# processor_breakout_conn.net
KiCad netlist of a schematic drawn in Altium Designer
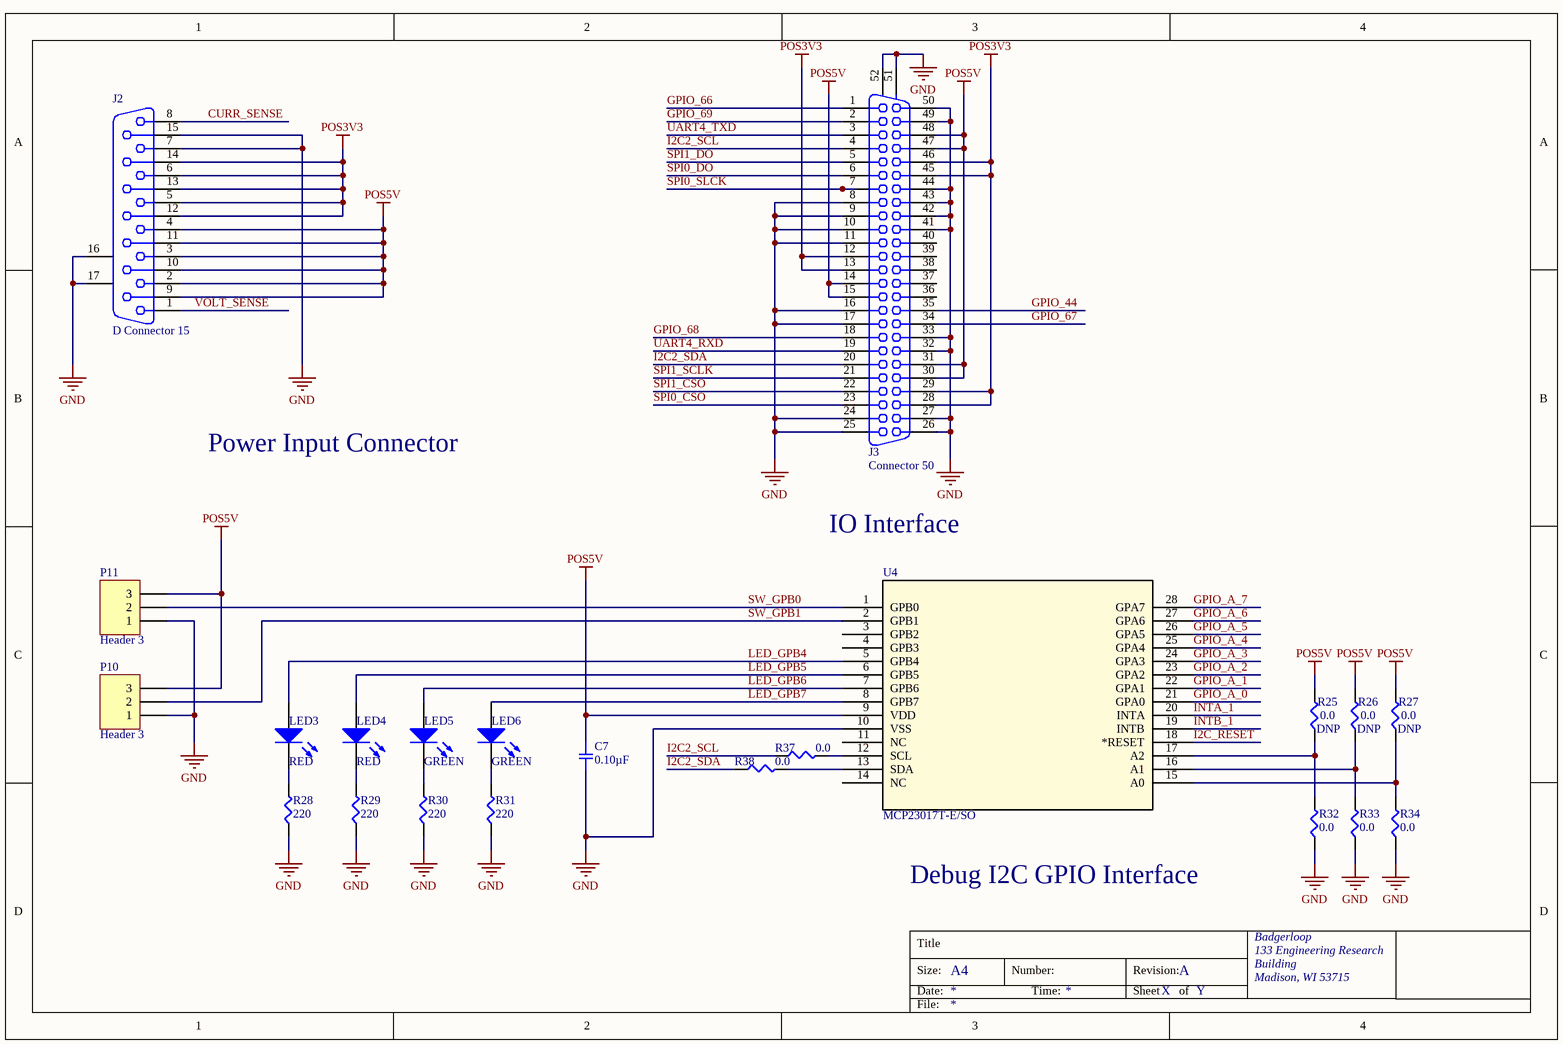
[diagram p0: processor_breakout_conn.SchDoc]

(export (version "E")
  (design (tool "Eeschema 10.0.6"))
  (components
    (comp (ref "C7")
      (value "0.10µF")
      (footprint "SMD-0603C")
      (description "CAP CER 0.1UF 100V X7R 0603")
      (fields
        (field (name "DIGI-KEY PART NUMBER") "490-13420-1-ND")
        (field (name "PART NUMBER") "GCJ188R72A104KA01D")
      )
      (libsource (lib "capacitor") (part "GCJ188R72A104KA01D"))
    )
    (comp (ref "J2")
      (value "D Connector 15")
      (footprint "DSUB1.385-2H15")
      (description "Receptacle Assembly, 15 Position, Right Angle")
      (fields (field (name "PUBLISHER") "Altium Limited"))
      (libsource (lib "connector") (part "D Connector 15"))
    )
    (comp (ref "J3")
      (value "Connector 50")
      (footprint "050DSUB1.27-H96")
      (description "Receptacle Header Assemby")
      (fields (field (name "PUBLISHER") "Altium Limited"))
      (libsource (lib "temp") (part "Connector 50"))
    )
    (comp (ref "LED3")
      (value "RED")
      (footprint "LED 0603 RED")
      (description "Red 631nm LED Indication - Discrete 2V 0603 (1608 Metric)")
      (fields (field (name "MANUFACTURER") "Lite-On Inc."))
      (libsource (lib "misc") (part "LED RED 0603"))
    )
    (comp (ref "LED4")
      (value "RED")
      (footprint "LED 0603 RED")
      (description "Red 631nm LED Indication - Discrete 2V 0603 (1608 Metric)")
      (fields (field (name "MANUFACTURER") "Lite-On Inc."))
      (libsource (lib "misc") (part "LED RED 0603"))
    )
    (comp (ref "LED5")
      (value "GREEN")
      (footprint "LED 0603 GREEN")
      (fields (field (name "MANUFACTURER") "Lite-On Inc."))
      (libsource (lib "misc") (part "LED GREEN 0603"))
    )
    (comp (ref "LED6")
      (value "GREEN")
      (footprint "LED 0603 GREEN")
      (fields (field (name "MANUFACTURER") "Lite-On Inc."))
      (libsource (lib "misc") (part "LED GREEN 0603"))
    )
    (comp (ref "P10")
      (value "Header 3")
      (footprint "Pin Header 1x3 TH Pitch 2.54mm")
      (description "Header, 3-Pin")
      (fields (field (name "PUBLISHER") "Altium Limited"))
      (libsource (lib "connector") (part "Header 3"))
    )
    (comp (ref "P11")
      (value "Header 3")
      (footprint "Pin Header 1x3 TH Pitch 2.54mm")
      (description "Header, 3-Pin")
      (fields (field (name "PUBLISHER") "Altium Limited"))
      (libsource (lib "connector") (part "Header 3"))
    )
    (comp (ref "R25")
      (value "0.0")
      (footprint "SMD-0402-RES")
      (description "RES SMD 0.0OHM JUMPER 1/10W 0402")
      (fields
        (field (name "PART NUMBER") "ERJ-2GE0R00X")
        (field (name "DIGI-KEY PART NUMBER") "P0.0JCT-ND")
        (field (name "DNP") "DNP")
      )
      (libsource (lib "resistor") (part "ERJ-2GE0R00X"))
    )
    (comp (ref "R26")
      (value "0.0")
      (footprint "SMD-0402-RES")
      (description "RES SMD 0.0OHM JUMPER 1/10W 0402")
      (fields
        (field (name "PART NUMBER") "ERJ-2GE0R00X")
        (field (name "DIGI-KEY PART NUMBER") "P0.0JCT-ND")
        (field (name "DNP") "DNP")
      )
      (libsource (lib "resistor") (part "ERJ-2GE0R00X"))
    )
    (comp (ref "R27")
      (value "0.0")
      (footprint "SMD-0402-RES")
      (description "RES SMD 0.0OHM JUMPER 1/10W 0402")
      (fields
        (field (name "PART NUMBER") "ERJ-2GE0R00X")
        (field (name "DIGI-KEY PART NUMBER") "P0.0JCT-ND")
        (field (name "DNP") "DNP")
      )
      (libsource (lib "resistor") (part "ERJ-2GE0R00X"))
    )
    (comp (ref "R28")
      (value "220")
      (footprint "SMD-0805-RES")
      (description "RES SMD 220 OHM 1% 1/8W 0805")
      (fields (field (name "PART NUMBER") "ERJ-6ENF2200V") (field (name "DIGI-KEY PART NUMBER") "P220CCT-ND"))
      (libsource (lib "resistor") (part "ERJ-6ENF2200V"))
    )
    (comp (ref "R29")
      (value "220")
      (footprint "SMD-0805-RES")
      (description "RES SMD 220 OHM 1% 1/8W 0805")
      (fields (field (name "PART NUMBER") "ERJ-6ENF2200V") (field (name "DIGI-KEY PART NUMBER") "P220CCT-ND"))
      (libsource (lib "resistor") (part "ERJ-6ENF2200V"))
    )
    (comp (ref "R30")
      (value "220")
      (footprint "SMD-0805-RES")
      (description "RES SMD 220 OHM 1% 1/8W 0805")
      (fields (field (name "PART NUMBER") "ERJ-6ENF2200V") (field (name "DIGI-KEY PART NUMBER") "P220CCT-ND"))
      (libsource (lib "resistor") (part "ERJ-6ENF2200V"))
    )
    (comp (ref "R31")
      (value "220")
      (footprint "SMD-0805-RES")
      (description "RES SMD 220 OHM 1% 1/8W 0805")
      (fields (field (name "PART NUMBER") "ERJ-6ENF2200V") (field (name "DIGI-KEY PART NUMBER") "P220CCT-ND"))
      (libsource (lib "resistor") (part "ERJ-6ENF2200V"))
    )
    (comp (ref "R32")
      (value "0.0")
      (footprint "SMD-0402-RES")
      (description "RES SMD 0.0OHM JUMPER 1/10W 0402")
      (fields (field (name "PART NUMBER") "ERJ-2GE0R00X") (field (name "DIGI-KEY PART NUMBER") "P0.0JCT-ND"))
      (libsource (lib "resistor") (part "ERJ-2GE0R00X"))
    )
    (comp (ref "R33")
      (value "0.0")
      (footprint "SMD-0402-RES")
      (description "RES SMD 0.0OHM JUMPER 1/10W 0402")
      (fields (field (name "PART NUMBER") "ERJ-2GE0R00X") (field (name "DIGI-KEY PART NUMBER") "P0.0JCT-ND"))
      (libsource (lib "resistor") (part "ERJ-2GE0R00X"))
    )
    (comp (ref "R34")
      (value "0.0")
      (footprint "SMD-0402-RES")
      (description "RES SMD 0.0OHM JUMPER 1/10W 0402")
      (fields (field (name "PART NUMBER") "ERJ-2GE0R00X") (field (name "DIGI-KEY PART NUMBER") "P0.0JCT-ND"))
      (libsource (lib "resistor") (part "ERJ-2GE0R00X"))
    )
    (comp (ref "R37")
      (value "0.0")
      (footprint "SMD-0402-RES")
      (description "RES SMD 0.0OHM JUMPER 1/10W 0402")
      (fields (field (name "PART NUMBER") "ERJ-2GE0R00X") (field (name "DIGI-KEY PART NUMBER") "P0.0JCT-ND"))
      (libsource (lib "resistor") (part "ERJ-2GE0R00X"))
    )
    (comp (ref "R38")
      (value "0.0")
      (footprint "SMD-0402-RES")
      (description "RES SMD 0.0OHM JUMPER 1/10W 0402")
      (fields (field (name "PART NUMBER") "ERJ-2GE0R00X") (field (name "DIGI-KEY PART NUMBER") "P0.0JCT-ND"))
      (libsource (lib "resistor") (part "ERJ-2GE0R00X"))
    )
    (comp (ref "U4")
      (value "MCP23017T-E/SO")
      (footprint "SOIC28-W_MC-M")
      (description "Imported")
      (libsource (lib "temp") (part "MCP23017T-E/SO"))
    )
  )
  (nets
    (net (code "1") (name "/CURR_SENSE") (class "Default")
      (node (ref "J2") (pin "8") (pinfunction "8_8") (pintype "passive"))
    )
    (net (code "2") (name "/GPIO_44") (class "Default")
      (node (ref "J3") (pin "35") (pinfunction "35_35") (pintype "passive"))
    )
    (net (code "3") (name "/GPIO_66") (class "Default")
      (node (ref "J3") (pin "1") (pinfunction "1_1") (pintype "passive"))
    )
    (net (code "4") (name "/GPIO_67") (class "Default")
      (node (ref "J3") (pin "34") (pinfunction "34_34") (pintype "passive"))
    )
    (net (code "5") (name "/GPIO_68") (class "Default")
      (node (ref "J3") (pin "18") (pinfunction "18_18") (pintype "passive"))
    )
    (net (code "6") (name "/GPIO_69") (class "Default")
      (node (ref "J3") (pin "2") (pinfunction "2_2") (pintype "passive"))
    )
    (net (code "7") (name "/GPIO_A_0") (class "Default")
      (node (ref "U4") (pin "21") (pinfunction "GPA0_21") (pintype "passive"))
    )
    (net (code "8") (name "/GPIO_A_1") (class "Default")
      (node (ref "U4") (pin "22") (pinfunction "GPA1_22") (pintype "passive"))
    )
    (net (code "9") (name "/GPIO_A_2") (class "Default")
      (node (ref "U4") (pin "23") (pinfunction "GPA2_23") (pintype "passive"))
    )
    (net (code "10") (name "/GPIO_A_3") (class "Default")
      (node (ref "U4") (pin "24") (pinfunction "GPA3_24") (pintype "passive"))
    )
    (net (code "11") (name "/GPIO_A_4") (class "Default")
      (node (ref "U4") (pin "25") (pinfunction "GPA4_25") (pintype "passive"))
    )
    (net (code "12") (name "/GPIO_A_5") (class "Default")
      (node (ref "U4") (pin "26") (pinfunction "GPA5_26") (pintype "passive"))
    )
    (net (code "13") (name "/GPIO_A_6") (class "Default")
      (node (ref "U4") (pin "27") (pinfunction "GPA6_27") (pintype "passive"))
    )
    (net (code "14") (name "/GPIO_A_7") (class "Default")
      (node (ref "U4") (pin "28") (pinfunction "GPA7_28") (pintype "passive"))
    )
    (net (code "15") (name "/I2C2_SCL") (class "Default")
      (node (ref "J3") (pin "4") (pinfunction "4_4") (pintype "passive"))
      (node (ref "R37") (pin "1") (pinfunction "1_1") (pintype "passive"))
    )
    (net (code "16") (name "/I2C2_SDA") (class "Default")
      (node (ref "J3") (pin "20") (pinfunction "20_20") (pintype "passive"))
      (node (ref "R38") (pin "1") (pinfunction "1_1") (pintype "passive"))
    )
    (net (code "17") (name "/I2C_RESET") (class "Default")
      (node (ref "U4") (pin "18") (pinfunction "*RESET_18") (pintype "passive"))
    )
    (net (code "18") (name "/INTA_1") (class "Default")
      (node (ref "U4") (pin "20") (pinfunction "INTA_20") (pintype "passive"))
    )
    (net (code "19") (name "/INTB_1") (class "Default")
      (node (ref "U4") (pin "19") (pinfunction "INTB_19") (pintype "passive"))
    )
    (net (code "20") (name "/LED_GPB4") (class "Default")
      (node (ref "LED3") (pin "1") (pinfunction "A_1") (pintype "passive"))
      (node (ref "U4") (pin "5") (pinfunction "GPB4_5") (pintype "passive"))
    )
    (net (code "21") (name "/LED_GPB5") (class "Default")
      (node (ref "LED4") (pin "1") (pinfunction "A_1") (pintype "passive"))
      (node (ref "U4") (pin "6") (pinfunction "GPB5_6") (pintype "passive"))
    )
    (net (code "22") (name "/LED_GPB6") (class "Default")
      (node (ref "LED5") (pin "1") (pinfunction "A_1") (pintype "passive"))
      (node (ref "U4") (pin "7") (pinfunction "GPB6_7") (pintype "passive"))
    )
    (net (code "23") (name "/LED_GPB7") (class "Default")
      (node (ref "LED6") (pin "1") (pinfunction "A_1") (pintype "passive"))
      (node (ref "U4") (pin "8") (pinfunction "GPB7_8") (pintype "passive"))
    )
    (net (code "24") (name "/SPI0_CSO") (class "Default")
      (node (ref "J3") (pin "23") (pinfunction "23_23") (pintype "passive"))
    )
    (net (code "25") (name "/SPI0_DO") (class "Default")
      (node (ref "J3") (pin "6") (pinfunction "6_6") (pintype "passive"))
    )
    (net (code "26") (name "/SPI0_SLCK") (class "Default")
      (node (ref "J3") (pin "7") (pinfunction "7_7") (pintype "passive"))
    )
    (net (code "27") (name "/SPI1_CSO") (class "Default")
      (node (ref "J3") (pin "22") (pinfunction "22_22") (pintype "passive"))
    )
    (net (code "28") (name "/SPI1_DO") (class "Default")
      (node (ref "J3") (pin "5") (pinfunction "5_5") (pintype "passive"))
    )
    (net (code "29") (name "/SPI1_SCLK") (class "Default")
      (node (ref "J3") (pin "21") (pinfunction "21_21") (pintype "passive"))
    )
    (net (code "30") (name "/SW_GPB0") (class "Default")
      (node (ref "P11") (pin "2") (pinfunction "2_2") (pintype "passive"))
      (node (ref "U4") (pin "1") (pinfunction "GPB0_1") (pintype "passive"))
    )
    (net (code "31") (name "/SW_GPB1") (class "Default")
      (node (ref "P10") (pin "2") (pinfunction "2_2") (pintype "passive"))
      (node (ref "U4") (pin "2") (pinfunction "GPB1_2") (pintype "passive"))
    )
    (net (code "32") (name "/UART4_RXD") (class "Default")
      (node (ref "J3") (pin "19") (pinfunction "19_19") (pintype "passive"))
    )
    (net (code "33") (name "/UART4_TXD") (class "Default")
      (node (ref "J3") (pin "3") (pinfunction "3_3") (pintype "passive"))
    )
    (net (code "34") (name "/VOLT_SENSE") (class "Default")
      (node (ref "J2") (pin "1") (pinfunction "1_1") (pintype "passive"))
    )
    (net (code "35") (name "GND") (class "Default")
      (node (ref "C7") (pin "2") (pinfunction "2_2") (pintype "passive"))
      (node (ref "J2") (pin "15") (pinfunction "15_15") (pintype "passive"))
      (node (ref "J2") (pin "16") (pinfunction "MH1_16") (pintype "passive"))
      (node (ref "J2") (pin "17") (pinfunction "MH2_17") (pintype "passive"))
      (node (ref "J2") (pin "7") (pinfunction "7_7") (pintype "passive"))
      (node (ref "J3") (pin "10") (pinfunction "10_10") (pintype "passive"))
      (node (ref "J3") (pin "11") (pinfunction "11_11") (pintype "passive"))
      (node (ref "J3") (pin "16") (pinfunction "16_16") (pintype "passive"))
      (node (ref "J3") (pin "17") (pinfunction "17_17") (pintype "passive"))
      (node (ref "J3") (pin "24") (pinfunction "24_24") (pintype "passive"))
      (node (ref "J3") (pin "25") (pinfunction "25_25") (pintype "passive"))
      (node (ref "J3") (pin "26") (pinfunction "26_26") (pintype "passive"))
      (node (ref "J3") (pin "27") (pinfunction "27_27") (pintype "passive"))
      (node (ref "J3") (pin "32") (pinfunction "32_32") (pintype "passive"))
      (node (ref "J3") (pin "33") (pinfunction "33_33") (pintype "passive"))
      (node (ref "J3") (pin "41") (pinfunction "41_41") (pintype "passive"))
      (node (ref "J3") (pin "42") (pinfunction "42_42") (pintype "passive"))
      (node (ref "J3") (pin "43") (pinfunction "43_43") (pintype "passive"))
      (node (ref "J3") (pin "44") (pinfunction "44_44") (pintype "passive"))
      (node (ref "J3") (pin "49") (pinfunction "49_49") (pintype "passive"))
      (node (ref "J3") (pin "50") (pinfunction "50_50") (pintype "passive"))
      (node (ref "J3") (pin "51") (pinfunction "51_51") (pintype "passive"))
      (node (ref "J3") (pin "52") (pinfunction "52_52") (pintype "passive"))
      (node (ref "J3") (pin "8") (pinfunction "8_8") (pintype "passive"))
      (node (ref "J3") (pin "9") (pinfunction "9_9") (pintype "passive"))
      (node (ref "P10") (pin "1") (pinfunction "1_1") (pintype "passive"))
      (node (ref "P11") (pin "1") (pinfunction "1_1") (pintype "passive"))
      (node (ref "R28") (pin "1") (pinfunction "1_1") (pintype "passive"))
      (node (ref "R29") (pin "1") (pinfunction "1_1") (pintype "passive"))
      (node (ref "R30") (pin "1") (pinfunction "1_1") (pintype "passive"))
      (node (ref "R31") (pin "1") (pinfunction "1_1") (pintype "passive"))
      (node (ref "R32") (pin "1") (pinfunction "1_1") (pintype "passive"))
      (node (ref "R33") (pin "1") (pinfunction "1_1") (pintype "passive"))
      (node (ref "R34") (pin "1") (pinfunction "1_1") (pintype "passive"))
      (node (ref "U4") (pin "10") (pinfunction "VSS_10") (pintype "passive"))
    )
    (net (code "36") (name "Net-(LED3-K)") (class "Default")
      (node (ref "LED3") (pin "2") (pinfunction "K_2") (pintype "passive"))
      (node (ref "R28") (pin "2") (pinfunction "2_2") (pintype "passive"))
    )
    (net (code "37") (name "Net-(LED4-K)") (class "Default")
      (node (ref "LED4") (pin "2") (pinfunction "K_2") (pintype "passive"))
      (node (ref "R29") (pin "2") (pinfunction "2_2") (pintype "passive"))
    )
    (net (code "38") (name "Net-(LED5-K)") (class "Default")
      (node (ref "LED5") (pin "2") (pinfunction "K_2") (pintype "passive"))
      (node (ref "R30") (pin "2") (pinfunction "2_2") (pintype "passive"))
    )
    (net (code "39") (name "Net-(LED6-K)") (class "Default")
      (node (ref "LED6") (pin "2") (pinfunction "K_2") (pintype "passive"))
      (node (ref "R31") (pin "2") (pinfunction "2_2") (pintype "passive"))
    )
    (net (code "40") (name "Net-(U4-A0)") (class "Default")
      (node (ref "R27") (pin "1") (pinfunction "1_1") (pintype "passive"))
      (node (ref "R34") (pin "2") (pinfunction "2_2") (pintype "passive"))
      (node (ref "U4") (pin "15") (pinfunction "A0_15") (pintype "passive"))
    )
    (net (code "41") (name "Net-(U4-A1)") (class "Default")
      (node (ref "R26") (pin "1") (pinfunction "1_1") (pintype "passive"))
      (node (ref "R33") (pin "2") (pinfunction "2_2") (pintype "passive"))
      (node (ref "U4") (pin "16") (pinfunction "A1_16") (pintype "passive"))
    )
    (net (code "42") (name "Net-(U4-A2)") (class "Default")
      (node (ref "R25") (pin "1") (pinfunction "1_1") (pintype "passive"))
      (node (ref "R32") (pin "2") (pinfunction "2_2") (pintype "passive"))
      (node (ref "U4") (pin "17") (pinfunction "A2_17") (pintype "passive"))
    )
    (net (code "43") (name "Net-(U4-SCL)") (class "Default")
      (node (ref "R37") (pin "2") (pinfunction "2_2") (pintype "passive"))
      (node (ref "U4") (pin "12") (pinfunction "SCL_12") (pintype "passive"))
    )
    (net (code "44") (name "Net-(U4-SDA)") (class "Default")
      (node (ref "R38") (pin "2") (pinfunction "2_2") (pintype "passive"))
      (node (ref "U4") (pin "13") (pinfunction "SDA_13") (pintype "passive"))
    )
    (net (code "45") (name "POS3V3") (class "Default")
      (node (ref "J2") (pin "12") (pinfunction "12_12") (pintype "passive"))
      (node (ref "J2") (pin "13") (pinfunction "13_13") (pintype "passive"))
      (node (ref "J2") (pin "14") (pinfunction "14_14") (pintype "passive"))
      (node (ref "J2") (pin "5") (pinfunction "5_5") (pintype "passive"))
      (node (ref "J2") (pin "6") (pinfunction "6_6") (pintype "passive"))
      (node (ref "J3") (pin "12") (pinfunction "12_12") (pintype "passive"))
      (node (ref "J3") (pin "13") (pinfunction "13_13") (pintype "passive"))
      (node (ref "J3") (pin "28") (pinfunction "28_28") (pintype "passive"))
      (node (ref "J3") (pin "29") (pinfunction "29_29") (pintype "passive"))
      (node (ref "J3") (pin "45") (pinfunction "45_45") (pintype "passive"))
      (node (ref "J3") (pin "46") (pinfunction "46_46") (pintype "passive"))
    )
    (net (code "46") (name "POS5V") (class "Default")
      (node (ref "C7") (pin "1") (pinfunction "1_1") (pintype "passive"))
      (node (ref "J2") (pin "10") (pinfunction "10_10") (pintype "passive"))
      (node (ref "J2") (pin "11") (pinfunction "11_11") (pintype "passive"))
      (node (ref "J2") (pin "2") (pinfunction "2_2") (pintype "passive"))
      (node (ref "J2") (pin "3") (pinfunction "3_3") (pintype "passive"))
      (node (ref "J2") (pin "4") (pinfunction "4_4") (pintype "passive"))
      (node (ref "J2") (pin "9") (pinfunction "9_9") (pintype "passive"))
      (node (ref "J3") (pin "14") (pinfunction "14_14") (pintype "passive"))
      (node (ref "J3") (pin "15") (pinfunction "15_15") (pintype "passive"))
      (node (ref "J3") (pin "30") (pinfunction "30_30") (pintype "passive"))
      (node (ref "J3") (pin "31") (pinfunction "31_31") (pintype "passive"))
      (node (ref "J3") (pin "47") (pinfunction "47_47") (pintype "passive"))
      (node (ref "J3") (pin "48") (pinfunction "48_48") (pintype "passive"))
      (node (ref "P10") (pin "3") (pinfunction "3_3") (pintype "passive"))
      (node (ref "P11") (pin "3") (pinfunction "3_3") (pintype "passive"))
      (node (ref "R25") (pin "2") (pinfunction "2_2") (pintype "passive"))
      (node (ref "R26") (pin "2") (pinfunction "2_2") (pintype "passive"))
      (node (ref "R27") (pin "2") (pinfunction "2_2") (pintype "passive"))
      (node (ref "U4") (pin "9") (pinfunction "VDD_9") (pintype "passive"))
    )
    (net (code "47") (name "unconnected-(J3-Pad36)") (class "Default")
      (node (ref "J3") (pin "36") (pinfunction "36_36") (pintype "passive"))
    )
    (net (code "48") (name "unconnected-(J3-Pad37)") (class "Default")
      (node (ref "J3") (pin "37") (pinfunction "37_37") (pintype "passive"))
    )
    (net (code "49") (name "unconnected-(J3-Pad38)") (class "Default")
      (node (ref "J3") (pin "38") (pinfunction "38_38") (pintype "passive"))
    )
    (net (code "50") (name "unconnected-(J3-Pad39)") (class "Default")
      (node (ref "J3") (pin "39") (pinfunction "39_39") (pintype "passive"))
    )
    (net (code "51") (name "unconnected-(J3-Pad40)") (class "Default")
      (node (ref "J3") (pin "40") (pinfunction "40_40") (pintype "passive"))
    )
    (net (code "52") (name "unconnected-(U4-GPB2-Pad3)") (class "Default")
      (node (ref "U4") (pin "3") (pinfunction "GPB2_3") (pintype "passive"))
    )
    (net (code "53") (name "unconnected-(U4-GPB3-Pad4)") (class "Default")
      (node (ref "U4") (pin "4") (pinfunction "GPB3_4") (pintype "passive"))
    )
    (net (code "54") (name "unconnected-(U4-NC-Pad11)") (class "Default")
      (node (ref "U4") (pin "11") (pinfunction "NC_11") (pintype "passive"))
    )
    (net (code "55") (name "unconnected-(U4-NC-Pad14)") (class "Default")
      (node (ref "U4") (pin "14") (pinfunction "NC_14") (pintype "passive"))
    )
  )
)
